# Sheet1.net
KiCad netlist of a schematic drawn in Altium Designer
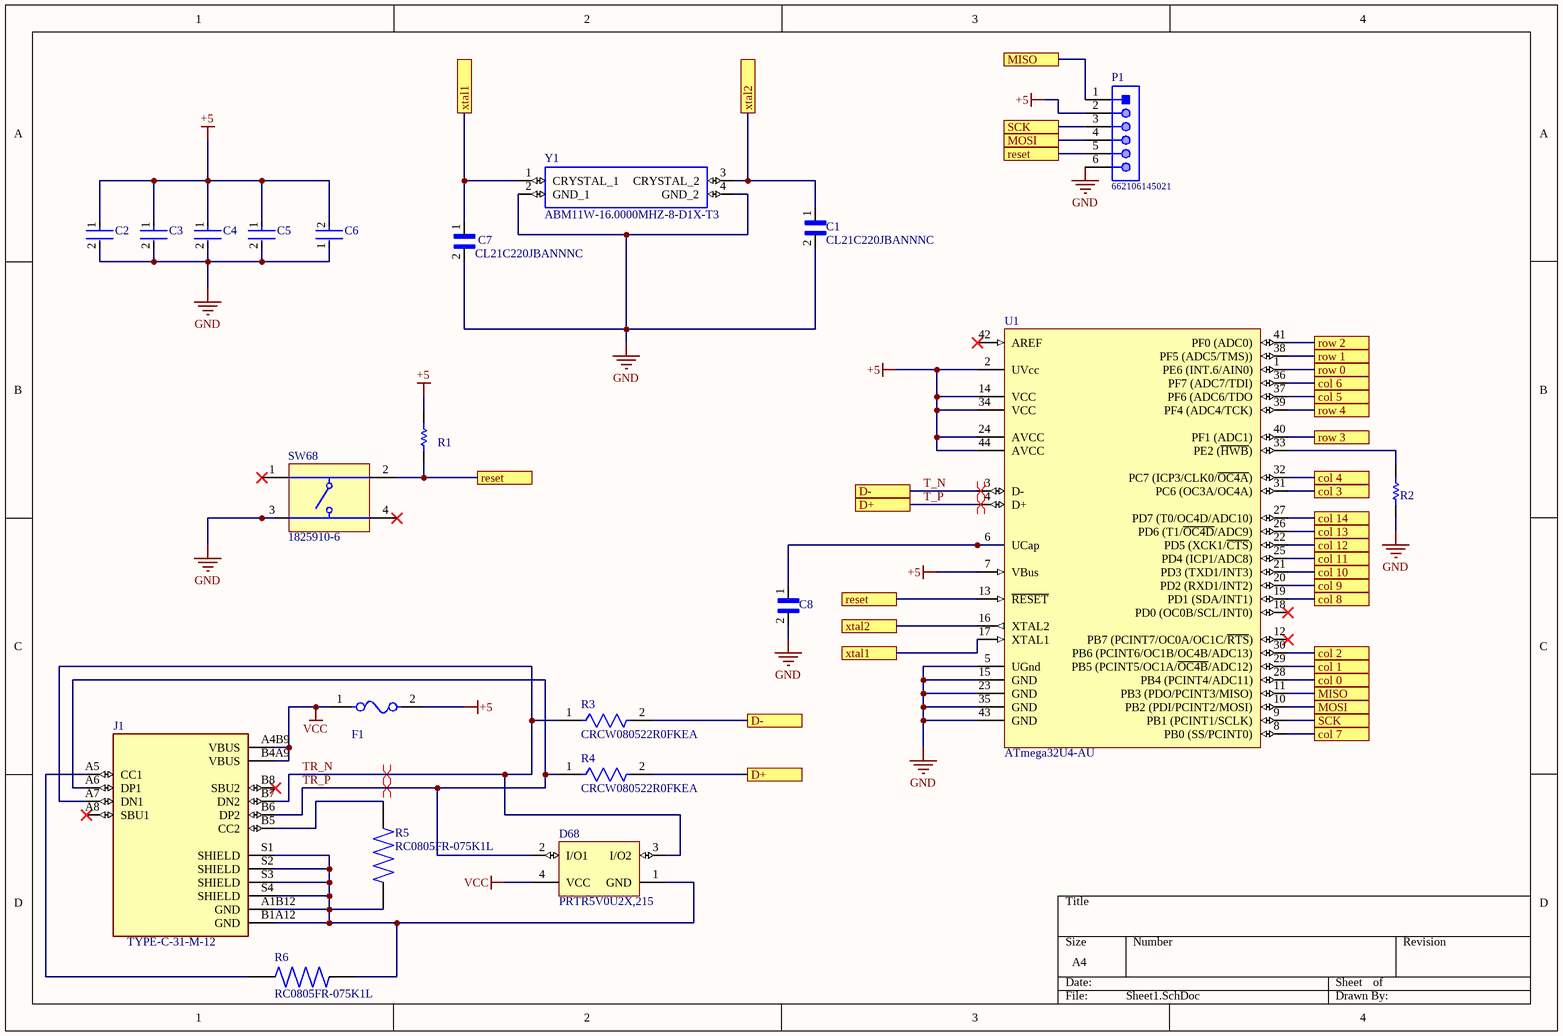
[diagram p0: Sheet1.SchDoc]

(export (version "E")
  (design (tool "Eeschema 10.0.6"))
  (components
    (comp (ref "C1")
      (value "CL21C220JBANNNC")
      (footprint "CAPC2012X140N")
      (description "22pF Â±5% 50V Ceramic Capacitor C0G, NP0 0805 _2012 Metric_")
      (fields (field (name "MF") "Samsung"))
      (libsource (lib "CL21C220JBANNNC") (part "CL21C220JBANNNC"))
    )
    (comp (ref "C2")
      (value "~")
      (footprint "FP-CL21-IPC_C")
      (description "CL21 Series 0805 100nF 50V ±10% Tolerance X7R Multilayer Ceramic Chip Capacitor")
      (fields (field (name "TOLERANCE") "10%") (field (name "VOLTAGE") "50V"))
      (libsource (lib "Altium Content Vault") (part "b4654b650e69147ec39a6b967a45e02"))
    )
    (comp (ref "C3")
      (value "~")
      (footprint "FP-CL21-IPC_C")
      (description "CL21 Series 0805 100nF 50V ±10% Tolerance X7R Multilayer Ceramic Chip Capacitor")
      (fields (field (name "TOLERANCE") "10%") (field (name "VOLTAGE") "50V"))
      (libsource (lib "Altium Content Vault") (part "b4654b650e69147ec39a6b967a45e02"))
    )
    (comp (ref "C4")
      (value "~")
      (footprint "FP-CL21-IPC_C")
      (description "CL21 Series 0805 100nF 50V ±10% Tolerance X7R Multilayer Ceramic Chip Capacitor")
      (fields (field (name "TOLERANCE") "10%") (field (name "VOLTAGE") "50V"))
      (libsource (lib "Altium Content Vault") (part "b4654b650e69147ec39a6b967a45e02"))
    )
    (comp (ref "C5")
      (value "~")
      (footprint "FP-CL21-IPC_C")
      (description "CL21 Series 0805 100nF 50V ±10% Tolerance X7R Multilayer Ceramic Chip Capacitor")
      (fields (field (name "TOLERANCE") "10%") (field (name "VOLTAGE") "50V"))
      (libsource (lib "Altium Content Vault") (part "b4654b650e69147ec39a6b967a45e02"))
    )
    (comp (ref "C6")
      (value "~")
      (footprint "FP-CL21B106KOQNNNE-MFG")
      (description "CAP CER 10UF 16V X7R 0805")
      (fields
        (field (name "MANUFACTURER PART NUMBER") "CL21B106KOQNNNE")
        (field (name "OCTOPART") "https://octopart.com/cl21b106koqnnne-samsung-19832289")
      )
      (libsource (lib "Altium Content Vault") (part "236180d848d6139a670b325ea6854c9"))
    )
    (comp (ref "C7")
      (value "CL21C220JBANNNC")
      (footprint "CAPC2012X140N")
      (description "22pF Â±5% 50V Ceramic Capacitor C0G, NP0 0805 _2012 Metric_")
      (fields (field (name "MF") "Samsung"))
      (libsource (lib "CL21C220JBANNNC") (part "CL21C220JBANNNC"))
    )
    (comp (ref "C8")
      (value "CL21B105KAFNNNE")
      (footprint "CAPC2012X140N")
      (description "1ÂµF Â±10% 25V Ceramic Capacitor X7R 0805 (2012 Metric)")
      (fields
        (field (name "MF") "Samsung Electro-Mechanics")
        (field (name "DIGI-KEY_PART_NUMBER") "1276-1066-1-ND")
      )
      (libsource (lib "CL21B105KAFNNNE") (part "CL21B105KAFNNNE"))
    )
    (comp (ref "D68")
      (value "PRTR5V0U2X,215")
      (footprint "NXP-SOT143B-4_V")
      (fields (field (name "MANUFACTURER") "NXP Semiconductors"))
      (libsource (lib "Altium Content Vault") (part "NXP-PRTR5V0U2X,215-4"))
    )
    (comp (ref "F1")
      (value "Fuse_Bel_0ZCJ0025AF2E_eec")
      (footprint "Bel_3216_0")
      (description "FUSE PTC RESET FUSE 24V 250MA 1206")
      (fields (field (name "PART NUMBER") "0ZCJ0025AF2E") (field (name "VOLTAGE") "24V"))
      (libsource (lib "Fuse_Bel_0ZCJ0025AF2E_eec") (part "Fuse_Bel_0ZCJ0025AF2E_eec"))
    )
    (comp (ref "J1")
      (value "TYPE-C-31-M-12")
      (footprint "HRO_TYPE-C-31-M-12")
      (description "USB Connectors 24 Receptacle 1 8.94*7.3mm RoHS")
      (fields (field (name "MF") "HRO Electronics Co., Ltd."))
      (libsource (lib "TYPE-C-31-M-12") (part "TYPE-C-31-M-12"))
    )
    (comp (ref "P1")
      (value "662106145021")
      (footprint "662106145021")
      (description "SMT Male Header WR-MPC3, with SMT Solder Tabs, Right Angled, Single Row, pitch 3 mm, 6 pins")
      (fields (field (name "MANUFACTURER") "Wurth Elektronik") (field (name "PUBLISHER") "WurthElektronik"))
      (libsource (lib "Altium Content Vault") (part "WE-CN-1P-M-R6"))
    )
    (comp (ref "R1")
      (value "RC0805FR-0710KL")
      (footprint "RESC2013X60X35NL10T20")
      (description "Chip Resistor, 10 KOhm, +/- 1%, 0.125 W, -55 to 155 degC, 0805 (2012 Metric), RoHS, Tape and Reel")
      (fields (field (name "MANUFACTURER") "Yageo"))
      (libsource (lib "Altium Content Vault") (part "RES-2"))
    )
    (comp (ref "R2")
      (value "RC0805FR-0710KL")
      (footprint "RESC2013X60X35NL10T20")
      (description "Chip Resistor, 10 KOhm, +/- 1%, 0.125 W, -55 to 155 degC, 0805 (2012 Metric), RoHS, Tape and Reel")
      (fields (field (name "MANUFACTURER") "Yageo"))
      (libsource (lib "Altium Content Vault") (part "RES-2"))
    )
    (comp (ref "R3")
      (value "CRCW080522R0FKEA")
      (footprint "FP-CRCW0805-e3-IPC_C")
      (description "RES Thick Film, 22Ω, 1%, 0.125W, 100ppm/°C, 0805")
      (fields (field (name "TOLERANCE") "1%"))
      (libsource (lib "Altium Content Vault") (part "1029c3af85768c4190bb7ad29bc67b5"))
    )
    (comp (ref "R4")
      (value "CRCW080522R0FKEA")
      (footprint "FP-CRCW0805-e3-IPC_C")
      (description "RES Thick Film, 22Ω, 1%, 0.125W, 100ppm/°C, 0805")
      (fields (field (name "TOLERANCE") "1%"))
      (libsource (lib "Altium Content Vault") (part "1029c3af85768c4190bb7ad29bc67b5"))
    )
    (comp (ref "R5")
      (value "RC0805FR-075K1L")
      (footprint "RESC2012X60N")
      (description "Resistor: thick film; SMD; 0805; 5.1kÎ©; 0.125W; Â±1%; -55Ã·155Â°C")
      (libsource (lib "RC0805FR-075K1L") (part "RC0805FR-075K1L"))
    )
    (comp (ref "R6")
      (value "RC0805FR-075K1L")
      (footprint "RESC2012X60N")
      (description "Resistor: thick film; SMD; 0805; 5.1kÎ©; 0.125W; Â±1%; -55Ã·155Â°C")
      (libsource (lib "RC0805FR-075K1L") (part "RC0805FR-075K1L"))
    )
    (comp (ref "SW68")
      (value "1825910-6")
      (footprint "TECO-1825910-6_V")
      (description "Tact Switch, SPST-NO, 0.05 A, -35 to 85 degC, 4-Pin THD, RoHS, Bulk")
      (fields (field (name "MANUFACTURER") "TE Connectivity"))
      (libsource (lib "Altium Content Vault") (part "SW-SPST-4_A"))
    )
    (comp (ref "U1")
      (value "ATmega32U4-AU")
      (footprint "44ML_M")
      (libsource (lib "Altium Content Vault") (part "MC-8B-ATM16U4-SQ44"))
    )
    (comp (ref "Y1")
      (value "ABM11W-16.0000MHZ-8-D1X-T3")
      (footprint "ABM11W300000MHZ4B1UT3")
      (description "16MHz Â±10ppm Crystal 8pF 200 Ohms 4-SMD, No Lead")
      (fields
        (field (name "MF") "Abracon")
        (field (name "BUYPART") "https://www.snapeda.com/parts/ABM11W-16.0000MHZ-8-D1X-T3/Abracon/view-part/2583382/?ref=eda")
      )
      (libsource (lib "ABM11W-16.0000MHZ-8-D1X-T3") (part "ABM11W-16.0000MHZ-8-D1X-T3"))
    )
  )
  (nets
    (net (code "1") (name "+5") (class "Default")
      (node (ref "C2") (pin "1") (pinfunction "1_1") (pintype "passive"))
      (node (ref "C3") (pin "1") (pinfunction "1_1") (pintype "passive"))
      (node (ref "C4") (pin "1") (pinfunction "1_1") (pintype "passive"))
      (node (ref "C5") (pin "1") (pinfunction "1_1") (pintype "passive"))
      (node (ref "C6") (pin "2") (pinfunction "2_2") (pintype "passive"))
      (node (ref "F1") (pin "2") (pinfunction "2_2") (pintype "passive"))
      (node (ref "P1") (pin "2") (pinfunction "2_2") (pintype "passive"))
      (node (ref "R1") (pin "2") (pinfunction "2_2") (pintype "passive"))
      (node (ref "U1") (pin "14") (pinfunction "VCC_14") (pintype "power_in"))
      (node (ref "U1") (pin "2") (pinfunction "UVcc_2") (pintype "power_in"))
      (node (ref "U1") (pin "24") (pinfunction "AVCC_24") (pintype "power_in"))
      (node (ref "U1") (pin "34") (pinfunction "VCC_34") (pintype "power_in"))
      (node (ref "U1") (pin "44") (pinfunction "AVCC_44") (pintype "power_in"))
      (node (ref "U1") (pin "7") (pinfunction "VBus_7") (pintype "input"))
    )
    (net (code "2") (name "/MISO") (class "Default")
      (node (ref "P1") (pin "1") (pinfunction "1_1") (pintype "passive"))
      (node (ref "U1") (pin "11") (pinfunction "PB3_(PDO/PCINT3/MISO)_11") (pintype "bidirectional"))
    )
    (net (code "3") (name "/MOSI") (class "Default")
      (node (ref "P1") (pin "4") (pinfunction "4_4") (pintype "passive"))
      (node (ref "U1") (pin "10") (pinfunction "PB2_(PDI/PCINT2/MOSI)_10") (pintype "bidirectional"))
    )
    (net (code "4") (name "/SCK") (class "Default")
      (node (ref "P1") (pin "3") (pinfunction "3_3") (pintype "passive"))
      (node (ref "U1") (pin "9") (pinfunction "PB1_(PCINT1/SCLK)_9") (pintype "bidirectional"))
    )
    (net (code "5") (name "/TR_N") (class "Default")
      (node (ref "D68") (pin "3") (pinfunction "I/O2_3") (pintype "bidirectional"))
      (node (ref "J1") (pin "A7") (pinfunction "DN1_A7") (pintype "bidirectional"))
      (node (ref "J1") (pin "B7") (pinfunction "DN2_B7") (pintype "bidirectional"))
      (node (ref "R3") (pin "1") (pinfunction "1_1") (pintype "passive"))
    )
    (net (code "6") (name "/TR_P") (class "Default")
      (node (ref "D68") (pin "2") (pinfunction "I/O1_2") (pintype "bidirectional"))
      (node (ref "J1") (pin "A6") (pinfunction "DP1_A6") (pintype "bidirectional"))
      (node (ref "J1") (pin "B6") (pinfunction "DP2_B6") (pintype "bidirectional"))
      (node (ref "R4") (pin "1") (pinfunction "1_1") (pintype "passive"))
    )
    (net (code "7") (name "/T_N") (class "Default")
      (node (ref "R3") (pin "2") (pinfunction "2_2") (pintype "passive"))
      (node (ref "U1") (pin "3") (pinfunction "D-_3") (pintype "bidirectional"))
    )
    (net (code "8") (name "/T_P") (class "Default")
      (node (ref "R4") (pin "2") (pinfunction "2_2") (pintype "passive"))
      (node (ref "U1") (pin "4") (pinfunction "D+_4") (pintype "bidirectional"))
    )
    (net (code "9") (name "/col 0") (class "Default")
      (node (ref "U1") (pin "28") (pinfunction "PB4_(PCINT4/ADC11)_28") (pintype "bidirectional"))
    )
    (net (code "10") (name "/col 1") (class "Default")
      (node (ref "U1") (pin "29") (pinfunction "PB5_(PCINT5/OC1A/~{OC4B}/ADC12)_29") (pintype "bidirectional"))
    )
    (net (code "11") (name "/col 2") (class "Default")
      (node (ref "U1") (pin "30") (pinfunction "PB6_(PCINT6/OC1B/OC4B/ADC13)_30") (pintype "bidirectional"))
    )
    (net (code "12") (name "/col 3") (class "Default")
      (node (ref "U1") (pin "31") (pinfunction "PC6_(OC3A/OC4A)_31") (pintype "bidirectional"))
    )
    (net (code "13") (name "/col 4") (class "Default")
      (node (ref "U1") (pin "32") (pinfunction "PC7_(ICP3/CLK0/~{OC4A})_32") (pintype "bidirectional"))
    )
    (net (code "14") (name "/col 5") (class "Default")
      (node (ref "U1") (pin "37") (pinfunction "PF6_(ADC6/TDO_37") (pintype "bidirectional"))
    )
    (net (code "15") (name "/col 6") (class "Default")
      (node (ref "U1") (pin "36") (pinfunction "PF7_(ADC7/TDI)_36") (pintype "bidirectional"))
    )
    (net (code "16") (name "/col 7") (class "Default")
      (node (ref "U1") (pin "8") (pinfunction "PB0_(SS/PCINT0)_8") (pintype "bidirectional"))
    )
    (net (code "17") (name "/col 8") (class "Default")
      (node (ref "U1") (pin "19") (pinfunction "PD1_(SDA/INT1)_19") (pintype "bidirectional"))
    )
    (net (code "18") (name "/col 9") (class "Default")
      (node (ref "U1") (pin "20") (pinfunction "PD2_(RXD1/INT2)_20") (pintype "bidirectional"))
    )
    (net (code "19") (name "/col 10") (class "Default")
      (node (ref "U1") (pin "21") (pinfunction "PD3_(TXD1/INT3)_21") (pintype "bidirectional"))
    )
    (net (code "20") (name "/col 11") (class "Default")
      (node (ref "U1") (pin "25") (pinfunction "PD4_(ICP1/ADC8)_25") (pintype "bidirectional"))
    )
    (net (code "21") (name "/col 12") (class "Default")
      (node (ref "U1") (pin "22") (pinfunction "PD5_(XCK1/~{CTS})_22") (pintype "bidirectional"))
    )
    (net (code "22") (name "/col 13") (class "Default")
      (node (ref "U1") (pin "26") (pinfunction "PD6_(T1/~{OC4D}/ADC9)_26") (pintype "bidirectional"))
    )
    (net (code "23") (name "/col 14") (class "Default")
      (node (ref "U1") (pin "27") (pinfunction "PD7_(T0/OC4D/ADC10)_27") (pintype "bidirectional"))
    )
    (net (code "24") (name "/reset") (class "Default")
      (node (ref "P1") (pin "5") (pinfunction "5_5") (pintype "passive"))
      (node (ref "R1") (pin "1") (pinfunction "1_1") (pintype "passive"))
      (node (ref "SW68") (pin "2") (pinfunction "2_2") (pintype "passive"))
      (node (ref "U1") (pin "13") (pinfunction "~{RESET}_13") (pintype "input"))
    )
    (net (code "25") (name "/row 0") (class "Default")
      (node (ref "U1") (pin "1") (pinfunction "PE6_(INT.6/AIN0)_1") (pintype "bidirectional"))
    )
    (net (code "26") (name "/row 1") (class "Default")
      (node (ref "U1") (pin "38") (pinfunction "PF5_(ADC5/TMS))_38") (pintype "bidirectional"))
    )
    (net (code "27") (name "/row 2") (class "Default")
      (node (ref "U1") (pin "41") (pinfunction "PF0_(ADC0)_41") (pintype "bidirectional"))
    )
    (net (code "28") (name "/row 3") (class "Default")
      (node (ref "U1") (pin "40") (pinfunction "PF1_(ADC1)_40") (pintype "bidirectional"))
    )
    (net (code "29") (name "/row 4") (class "Default")
      (node (ref "U1") (pin "39") (pinfunction "PF4_(ADC4/TCK)_39") (pintype "bidirectional"))
    )
    (net (code "30") (name "/xtal1") (class "Default")
      (node (ref "C7") (pin "1") (pinfunction "1_1") (pintype "passive"))
      (node (ref "U1") (pin "17") (pinfunction "XTAL1_17") (pintype "input"))
      (node (ref "Y1") (pin "1") (pinfunction "CRYSTAL_1_1") (pintype "bidirectional"))
    )
    (net (code "31") (name "/xtal2") (class "Default")
      (node (ref "C1") (pin "1") (pinfunction "1_1") (pintype "passive"))
      (node (ref "U1") (pin "16") (pinfunction "XTAL2_16") (pintype "output"))
      (node (ref "Y1") (pin "3") (pinfunction "CRYSTAL_2_3") (pintype "bidirectional"))
    )
    (net (code "32") (name "GND") (class "Default")
      (node (ref "C1") (pin "2") (pinfunction "2_2") (pintype "passive"))
      (node (ref "C2") (pin "2") (pinfunction "2_2") (pintype "passive"))
      (node (ref "C3") (pin "2") (pinfunction "2_2") (pintype "passive"))
      (node (ref "C4") (pin "2") (pinfunction "2_2") (pintype "passive"))
      (node (ref "C5") (pin "2") (pinfunction "2_2") (pintype "passive"))
      (node (ref "C6") (pin "1") (pinfunction "1_1") (pintype "passive"))
      (node (ref "C7") (pin "2") (pinfunction "2_2") (pintype "passive"))
      (node (ref "C8") (pin "2") (pinfunction "2_2") (pintype "passive"))
      (node (ref "P1") (pin "6") (pinfunction "6_6") (pintype "passive"))
      (node (ref "R2") (pin "1") (pinfunction "1_1") (pintype "passive"))
      (node (ref "SW68") (pin "3") (pinfunction "3_3") (pintype "passive"))
      (node (ref "U1") (pin "15") (pinfunction "GND_15") (pintype "power_in"))
      (node (ref "U1") (pin "23") (pinfunction "GND_23") (pintype "power_in"))
      (node (ref "U1") (pin "35") (pinfunction "GND_35") (pintype "power_in"))
      (node (ref "U1") (pin "43") (pinfunction "GND_43") (pintype "power_in"))
      (node (ref "U1") (pin "5") (pinfunction "UGnd_5") (pintype "power_in"))
      (node (ref "Y1") (pin "2") (pinfunction "GND_1_2") (pintype "bidirectional"))
      (node (ref "Y1") (pin "4") (pinfunction "GND_2_4") (pintype "bidirectional"))
    )
    (net (code "33") (name "Net-(D68-GND)") (class "Default")
      (node (ref "D68") (pin "1") (pinfunction "GND_1") (pintype "power_in"))
      (node (ref "J1") (pin "A1B12") (pinfunction "GND_A1B12") (pintype "power_in"))
      (node (ref "J1") (pin "B1A12") (pinfunction "GND_B1A12") (pintype "power_in"))
      (node (ref "J1") (pin "S1") (pinfunction "SHIELD_S1") (pintype "passive"))
      (node (ref "J1") (pin "S2") (pinfunction "SHIELD_S2") (pintype "passive"))
      (node (ref "J1") (pin "S3") (pinfunction "SHIELD_S3") (pintype "passive"))
      (node (ref "J1") (pin "S4") (pinfunction "SHIELD_S4") (pintype "passive"))
      (node (ref "R5") (pin "1") (pinfunction "1_1") (pintype "passive"))
      (node (ref "R6") (pin "2") (pinfunction "2_2") (pintype "passive"))
    )
    (net (code "34") (name "Net-(J1-CC1)") (class "Default")
      (node (ref "J1") (pin "A5") (pinfunction "CC1_A5") (pintype "bidirectional"))
      (node (ref "R6") (pin "1") (pinfunction "1_1") (pintype "passive"))
    )
    (net (code "35") (name "Net-(J1-CC2)") (class "Default")
      (node (ref "J1") (pin "B5") (pinfunction "CC2_B5") (pintype "bidirectional"))
      (node (ref "R5") (pin "2") (pinfunction "2_2") (pintype "passive"))
    )
    (net (code "36") (name "Net-(U1-PE2_(~{HWB}))") (class "Default")
      (node (ref "R2") (pin "2") (pinfunction "2_2") (pintype "passive"))
      (node (ref "U1") (pin "33") (pinfunction "PE2_(~{HWB})_33") (pintype "bidirectional"))
    )
    (net (code "37") (name "Net-(U1-UCap)") (class "Default")
      (node (ref "C8") (pin "1") (pinfunction "1_1") (pintype "passive"))
      (node (ref "U1") (pin "6") (pinfunction "UCap_6") (pintype "passive"))
    )
    (net (code "38") (name "VCC") (class "Default")
      (node (ref "D68") (pin "4") (pinfunction "VCC_4") (pintype "power_in"))
      (node (ref "F1") (pin "1") (pinfunction "1_1") (pintype "passive"))
      (node (ref "J1") (pin "A4B9") (pinfunction "VBUS_A4B9") (pintype "power_in"))
      (node (ref "J1") (pin "B4A9") (pinfunction "VBUS_B4A9") (pintype "power_in"))
    )
    (net (code "39") (name "unconnected-(J1-SBU1-PadA8)") (class "Default")
      (node (ref "J1") (pin "A8") (pinfunction "SBU1_A8") (pintype "bidirectional+no_connect"))
    )
    (net (code "40") (name "unconnected-(J1-SBU2-PadB8)") (class "Default")
      (node (ref "J1") (pin "B8") (pinfunction "SBU2_B8") (pintype "bidirectional+no_connect"))
    )
    (net (code "41") (name "unconnected-(SW68-Pad1)") (class "Default")
      (node (ref "SW68") (pin "1") (pinfunction "1_1") (pintype "passive+no_connect"))
    )
    (net (code "42") (name "unconnected-(SW68-Pad4)") (class "Default")
      (node (ref "SW68") (pin "4") (pinfunction "4_4") (pintype "passive+no_connect"))
    )
    (net (code "43") (name "unconnected-(U1-AREF-Pad42)") (class "Default")
      (node (ref "U1") (pin "42") (pinfunction "AREF_42") (pintype "input+no_connect"))
    )
    (net (code "44") (name "unconnected-(U1-PB7_(PCINT7{slash}OC0A{slash}OC1C{slash}~{RTS})-Pad12)") (class "Default")
      (node (ref "U1") (pin "12") (pinfunction "PB7_(PCINT7/OC0A/OC1C/~{RTS})_12") (pintype "bidirectional+no_connect"))
    )
    (net (code "45") (name "unconnected-(U1-PD0_(OC0B{slash}SCL{slash}INT0)-Pad18)") (class "Default")
      (node (ref "U1") (pin "18") (pinfunction "PD0_(OC0B/SCL/INT0)_18") (pintype "bidirectional+no_connect"))
    )
  )
)
